# ForPlants.net
KiCad netlist of a schematic drawn in EAGLE
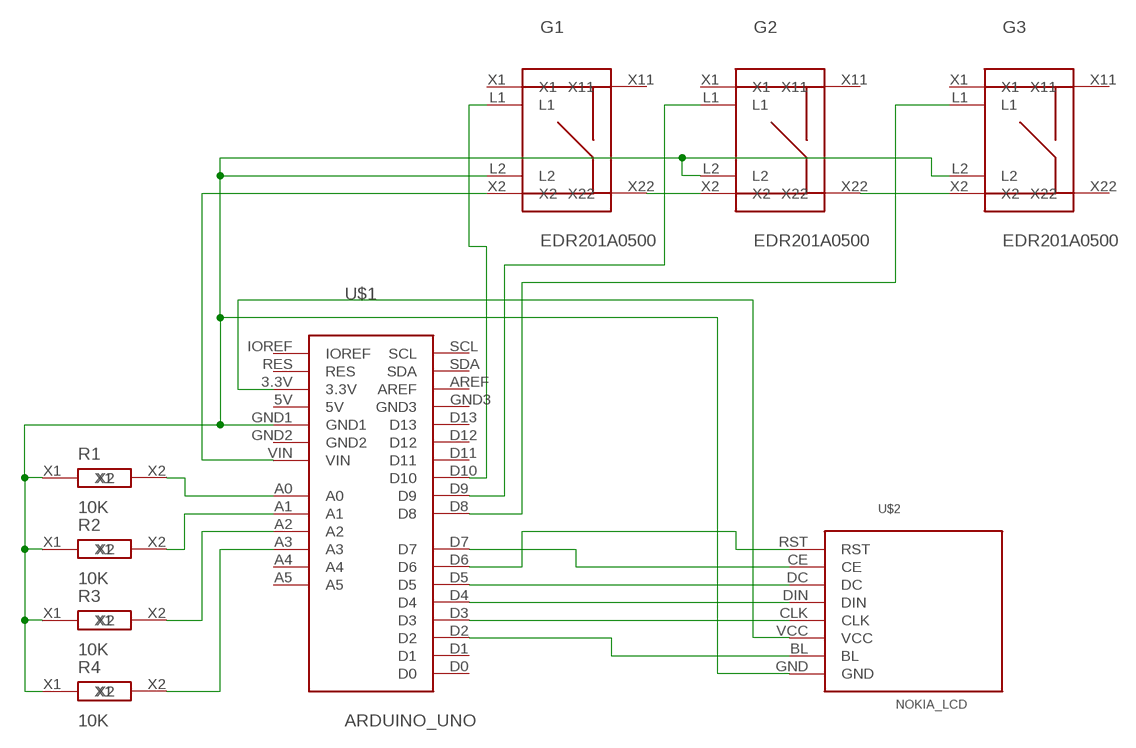
[diagram p0: schematic, sheet 1]

(export (version "E")
  (design (tool "Eeschema 10.0.6"))
  (components
    (comp (ref "G1")
      (value "EDR201A0500")
      (footprint "eagle-import:EDR201A0500")
      (libsource (lib "eagle-import") (part "EDR201A0500"))
    )
    (comp (ref "G2")
      (value "EDR201A0500")
      (footprint "eagle-import:EDR201A0500")
      (libsource (lib "eagle-import") (part "EDR201A0500"))
    )
    (comp (ref "G3")
      (value "EDR201A0500")
      (footprint "eagle-import:EDR201A0500")
      (libsource (lib "eagle-import") (part "EDR201A0500"))
    )
    (comp (ref "R1")
      (value "10K")
      (footprint "eagle-import:SMD_2.1X1.25")
      (libsource (lib "eagle-import") (part "R_SMD_2.1X1.25"))
    )
    (comp (ref "R2")
      (value "10K")
      (footprint "eagle-import:SMD_2.1X1.25")
      (libsource (lib "eagle-import") (part "R_SMD_2.1X1.25"))
    )
    (comp (ref "R3")
      (value "10K")
      (footprint "eagle-import:SMD_2.1X1.25")
      (libsource (lib "eagle-import") (part "R_SMD_2.1X1.25"))
    )
    (comp (ref "R4")
      (value "10K")
      (footprint "eagle-import:SMD_2.1X1.25")
      (libsource (lib "eagle-import") (part "R_SMD_2.1X1.25"))
    )
    (comp (ref "U$1")
      (value "ARDUINO_UNO")
      (footprint "eagle-import:ARDUINO_UNO")
      (libsource (lib "eagle-import") (part "ARDUINO_UNO"))
    )
    (comp (ref "U$2")
      (value "NOKIA_LCD")
      (footprint "eagle-import:NOKIA_LCD")
      (libsource (lib "eagle-import") (part "NOKIA_LCD"))
    )
  )
  (nets
    (net (code "1") (name "Net-(G1-PadL1)") (class "Default")
      (node (ref "G1") (pin "L1") (pinfunction "L1_L1") (pintype "bidirectional"))
      (node (ref "U$1") (pin "D10") (pinfunction "D10_D10") (pintype "bidirectional"))
    )
    (net (code "2") (name "Net-(G1-PadL2)") (class "Default")
      (node (ref "G1") (pin "L2") (pinfunction "L2_L2") (pintype "bidirectional"))
      (node (ref "G2") (pin "L2") (pinfunction "L2_L2") (pintype "bidirectional"))
      (node (ref "G3") (pin "L2") (pinfunction "L2_L2") (pintype "bidirectional"))
      (node (ref "R1") (pin "X1") (pinfunction "X1_X1") (pintype "bidirectional"))
      (node (ref "R2") (pin "X1") (pinfunction "X1_X1") (pintype "bidirectional"))
      (node (ref "R3") (pin "X1") (pinfunction "X1_X1") (pintype "bidirectional"))
      (node (ref "R4") (pin "X1") (pinfunction "X1_X1") (pintype "bidirectional"))
      (node (ref "U$1") (pin "GND1") (pinfunction "GND1_GND1") (pintype "bidirectional"))
      (node (ref "U$2") (pin "GND") (pinfunction "GND_GND") (pintype "bidirectional"))
    )
    (net (code "3") (name "Net-(G1-PadX2)") (class "Default")
      (node (ref "G1") (pin "X2") (pinfunction "X2_X2") (pintype "bidirectional"))
      (node (ref "U$1") (pin "VIN") (pinfunction "VIN_VIN") (pintype "bidirectional"))
    )
    (net (code "4") (name "Net-(G1-PadX22)") (class "Default")
      (node (ref "G1") (pin "X22") (pinfunction "X22_X22") (pintype "bidirectional"))
      (node (ref "G2") (pin "X2") (pinfunction "X2_X2") (pintype "bidirectional"))
    )
    (net (code "5") (name "Net-(G2-PadL1)") (class "Default")
      (node (ref "G2") (pin "L1") (pinfunction "L1_L1") (pintype "bidirectional"))
      (node (ref "U$1") (pin "D9") (pinfunction "D9_D9") (pintype "bidirectional"))
    )
    (net (code "6") (name "Net-(G2-PadX22)") (class "Default")
      (node (ref "G2") (pin "X22") (pinfunction "X22_X22") (pintype "bidirectional"))
      (node (ref "G3") (pin "X2") (pinfunction "X2_X2") (pintype "bidirectional"))
    )
    (net (code "7") (name "Net-(G3-PadL1)") (class "Default")
      (node (ref "G3") (pin "L1") (pinfunction "L1_L1") (pintype "bidirectional"))
      (node (ref "U$1") (pin "D8") (pinfunction "D8_D8") (pintype "bidirectional"))
    )
    (net (code "8") (name "Net-(R1-PadX2)") (class "Default")
      (node (ref "R1") (pin "X2") (pinfunction "X2_X2") (pintype "bidirectional"))
      (node (ref "U$1") (pin "A0") (pinfunction "A0_A0") (pintype "bidirectional"))
    )
    (net (code "9") (name "Net-(R2-PadX2)") (class "Default")
      (node (ref "R2") (pin "X2") (pinfunction "X2_X2") (pintype "bidirectional"))
      (node (ref "U$1") (pin "A1") (pinfunction "A1_A1") (pintype "bidirectional"))
    )
    (net (code "10") (name "Net-(R3-PadX2)") (class "Default")
      (node (ref "R3") (pin "X2") (pinfunction "X2_X2") (pintype "bidirectional"))
      (node (ref "U$1") (pin "A2") (pinfunction "A2_A2") (pintype "bidirectional"))
    )
    (net (code "11") (name "Net-(R4-PadX2)") (class "Default")
      (node (ref "R4") (pin "X2") (pinfunction "X2_X2") (pintype "bidirectional"))
      (node (ref "U$1") (pin "A3") (pinfunction "A3_A3") (pintype "bidirectional"))
    )
    (net (code "12") (name "Net-(U$1-Pad3.3V)") (class "Default")
      (node (ref "U$1") (pin "3.3V") (pinfunction "3.3V_3.3V") (pintype "bidirectional"))
      (node (ref "U$2") (pin "VCC") (pinfunction "VCC_VCC") (pintype "bidirectional"))
    )
    (net (code "13") (name "Net-(U$1-PadD2)") (class "Default")
      (node (ref "U$1") (pin "D2") (pinfunction "D2_D2") (pintype "bidirectional"))
      (node (ref "U$2") (pin "BL") (pinfunction "BL_BL") (pintype "bidirectional"))
    )
    (net (code "14") (name "Net-(U$1-PadD3)") (class "Default")
      (node (ref "U$1") (pin "D3") (pinfunction "D3_D3") (pintype "bidirectional"))
      (node (ref "U$2") (pin "CLK") (pinfunction "CLK_CLK") (pintype "bidirectional"))
    )
    (net (code "15") (name "Net-(U$1-PadD4)") (class "Default")
      (node (ref "U$1") (pin "D4") (pinfunction "D4_D4") (pintype "bidirectional"))
      (node (ref "U$2") (pin "DIN") (pinfunction "DIN_DIN") (pintype "bidirectional"))
    )
    (net (code "16") (name "Net-(U$1-PadD5)") (class "Default")
      (node (ref "U$1") (pin "D5") (pinfunction "D5_D5") (pintype "bidirectional"))
      (node (ref "U$2") (pin "DC") (pinfunction "DC_DC") (pintype "bidirectional"))
    )
    (net (code "17") (name "Net-(U$1-PadD6)") (class "Default")
      (node (ref "U$1") (pin "D6") (pinfunction "D6_D6") (pintype "bidirectional"))
      (node (ref "U$2") (pin "RST") (pinfunction "RST_RST") (pintype "bidirectional"))
    )
    (net (code "18") (name "Net-(U$1-PadD7)") (class "Default")
      (node (ref "U$1") (pin "D7") (pinfunction "D7_D7") (pintype "bidirectional"))
      (node (ref "U$2") (pin "CE") (pinfunction "CE_CE") (pintype "bidirectional"))
    )
    (net (code "19") (name "unconnected-(G1-PadX1)") (class "Default")
      (node (ref "G1") (pin "X1") (pinfunction "X1_X1") (pintype "bidirectional"))
    )
    (net (code "20") (name "unconnected-(G1-PadX11)") (class "Default")
      (node (ref "G1") (pin "X11") (pinfunction "X11_X11") (pintype "bidirectional"))
    )
    (net (code "21") (name "unconnected-(G2-PadX1)") (class "Default")
      (node (ref "G2") (pin "X1") (pinfunction "X1_X1") (pintype "bidirectional"))
    )
    (net (code "22") (name "unconnected-(G2-PadX11)") (class "Default")
      (node (ref "G2") (pin "X11") (pinfunction "X11_X11") (pintype "bidirectional"))
    )
    (net (code "23") (name "unconnected-(G3-PadX1)") (class "Default")
      (node (ref "G3") (pin "X1") (pinfunction "X1_X1") (pintype "bidirectional"))
    )
    (net (code "24") (name "unconnected-(G3-PadX11)") (class "Default")
      (node (ref "G3") (pin "X11") (pinfunction "X11_X11") (pintype "bidirectional"))
    )
    (net (code "25") (name "unconnected-(G3-PadX22)") (class "Default")
      (node (ref "G3") (pin "X22") (pinfunction "X22_X22") (pintype "bidirectional"))
    )
    (net (code "26") (name "unconnected-(U$1-Pad5V)") (class "Default")
      (node (ref "U$1") (pin "5V") (pinfunction "5V_5V") (pintype "bidirectional"))
    )
    (net (code "27") (name "unconnected-(U$1-PadA4)") (class "Default")
      (node (ref "U$1") (pin "A4") (pinfunction "A4_A4") (pintype "bidirectional"))
    )
    (net (code "28") (name "unconnected-(U$1-PadA5)") (class "Default")
      (node (ref "U$1") (pin "A5") (pinfunction "A5_A5") (pintype "bidirectional"))
    )
    (net (code "29") (name "unconnected-(U$1-PadAREF)") (class "Default")
      (node (ref "U$1") (pin "AREF") (pinfunction "AREF_AREF") (pintype "bidirectional"))
    )
    (net (code "30") (name "unconnected-(U$1-PadD0)") (class "Default")
      (node (ref "U$1") (pin "D0") (pinfunction "D0_D0") (pintype "bidirectional"))
    )
    (net (code "31") (name "unconnected-(U$1-PadD1)") (class "Default")
      (node (ref "U$1") (pin "D1") (pinfunction "D1_D1") (pintype "bidirectional"))
    )
    (net (code "32") (name "unconnected-(U$1-PadD11)") (class "Default")
      (node (ref "U$1") (pin "D11") (pinfunction "D11_D11") (pintype "bidirectional"))
    )
    (net (code "33") (name "unconnected-(U$1-PadD12)") (class "Default")
      (node (ref "U$1") (pin "D12") (pinfunction "D12_D12") (pintype "bidirectional"))
    )
    (net (code "34") (name "unconnected-(U$1-PadD13)") (class "Default")
      (node (ref "U$1") (pin "D13") (pinfunction "D13_D13") (pintype "bidirectional"))
    )
    (net (code "35") (name "unconnected-(U$1-PadGND2)") (class "Default")
      (node (ref "U$1") (pin "GND2") (pinfunction "GND2_GND2") (pintype "bidirectional"))
    )
    (net (code "36") (name "unconnected-(U$1-PadGND3)") (class "Default")
      (node (ref "U$1") (pin "GND3") (pinfunction "GND3_GND3") (pintype "bidirectional"))
    )
    (net (code "37") (name "unconnected-(U$1-PadIOREF)") (class "Default")
      (node (ref "U$1") (pin "IOREF") (pinfunction "IOREF_IOREF") (pintype "bidirectional"))
    )
    (net (code "38") (name "unconnected-(U$1-PadRES)") (class "Default")
      (node (ref "U$1") (pin "RES") (pinfunction "RES_RES") (pintype "bidirectional"))
    )
    (net (code "39") (name "unconnected-(U$1-PadSCL)") (class "Default")
      (node (ref "U$1") (pin "SCL") (pinfunction "SCL_SCL") (pintype "bidirectional"))
    )
    (net (code "40") (name "unconnected-(U$1-PadSDA)") (class "Default")
      (node (ref "U$1") (pin "SDA") (pinfunction "SDA_SDA") (pintype "bidirectional"))
    )
  )
)
